# IRIS-EXT-04-BRK_Top.net
KiCad netlist of a schematic drawn in Altium Designer
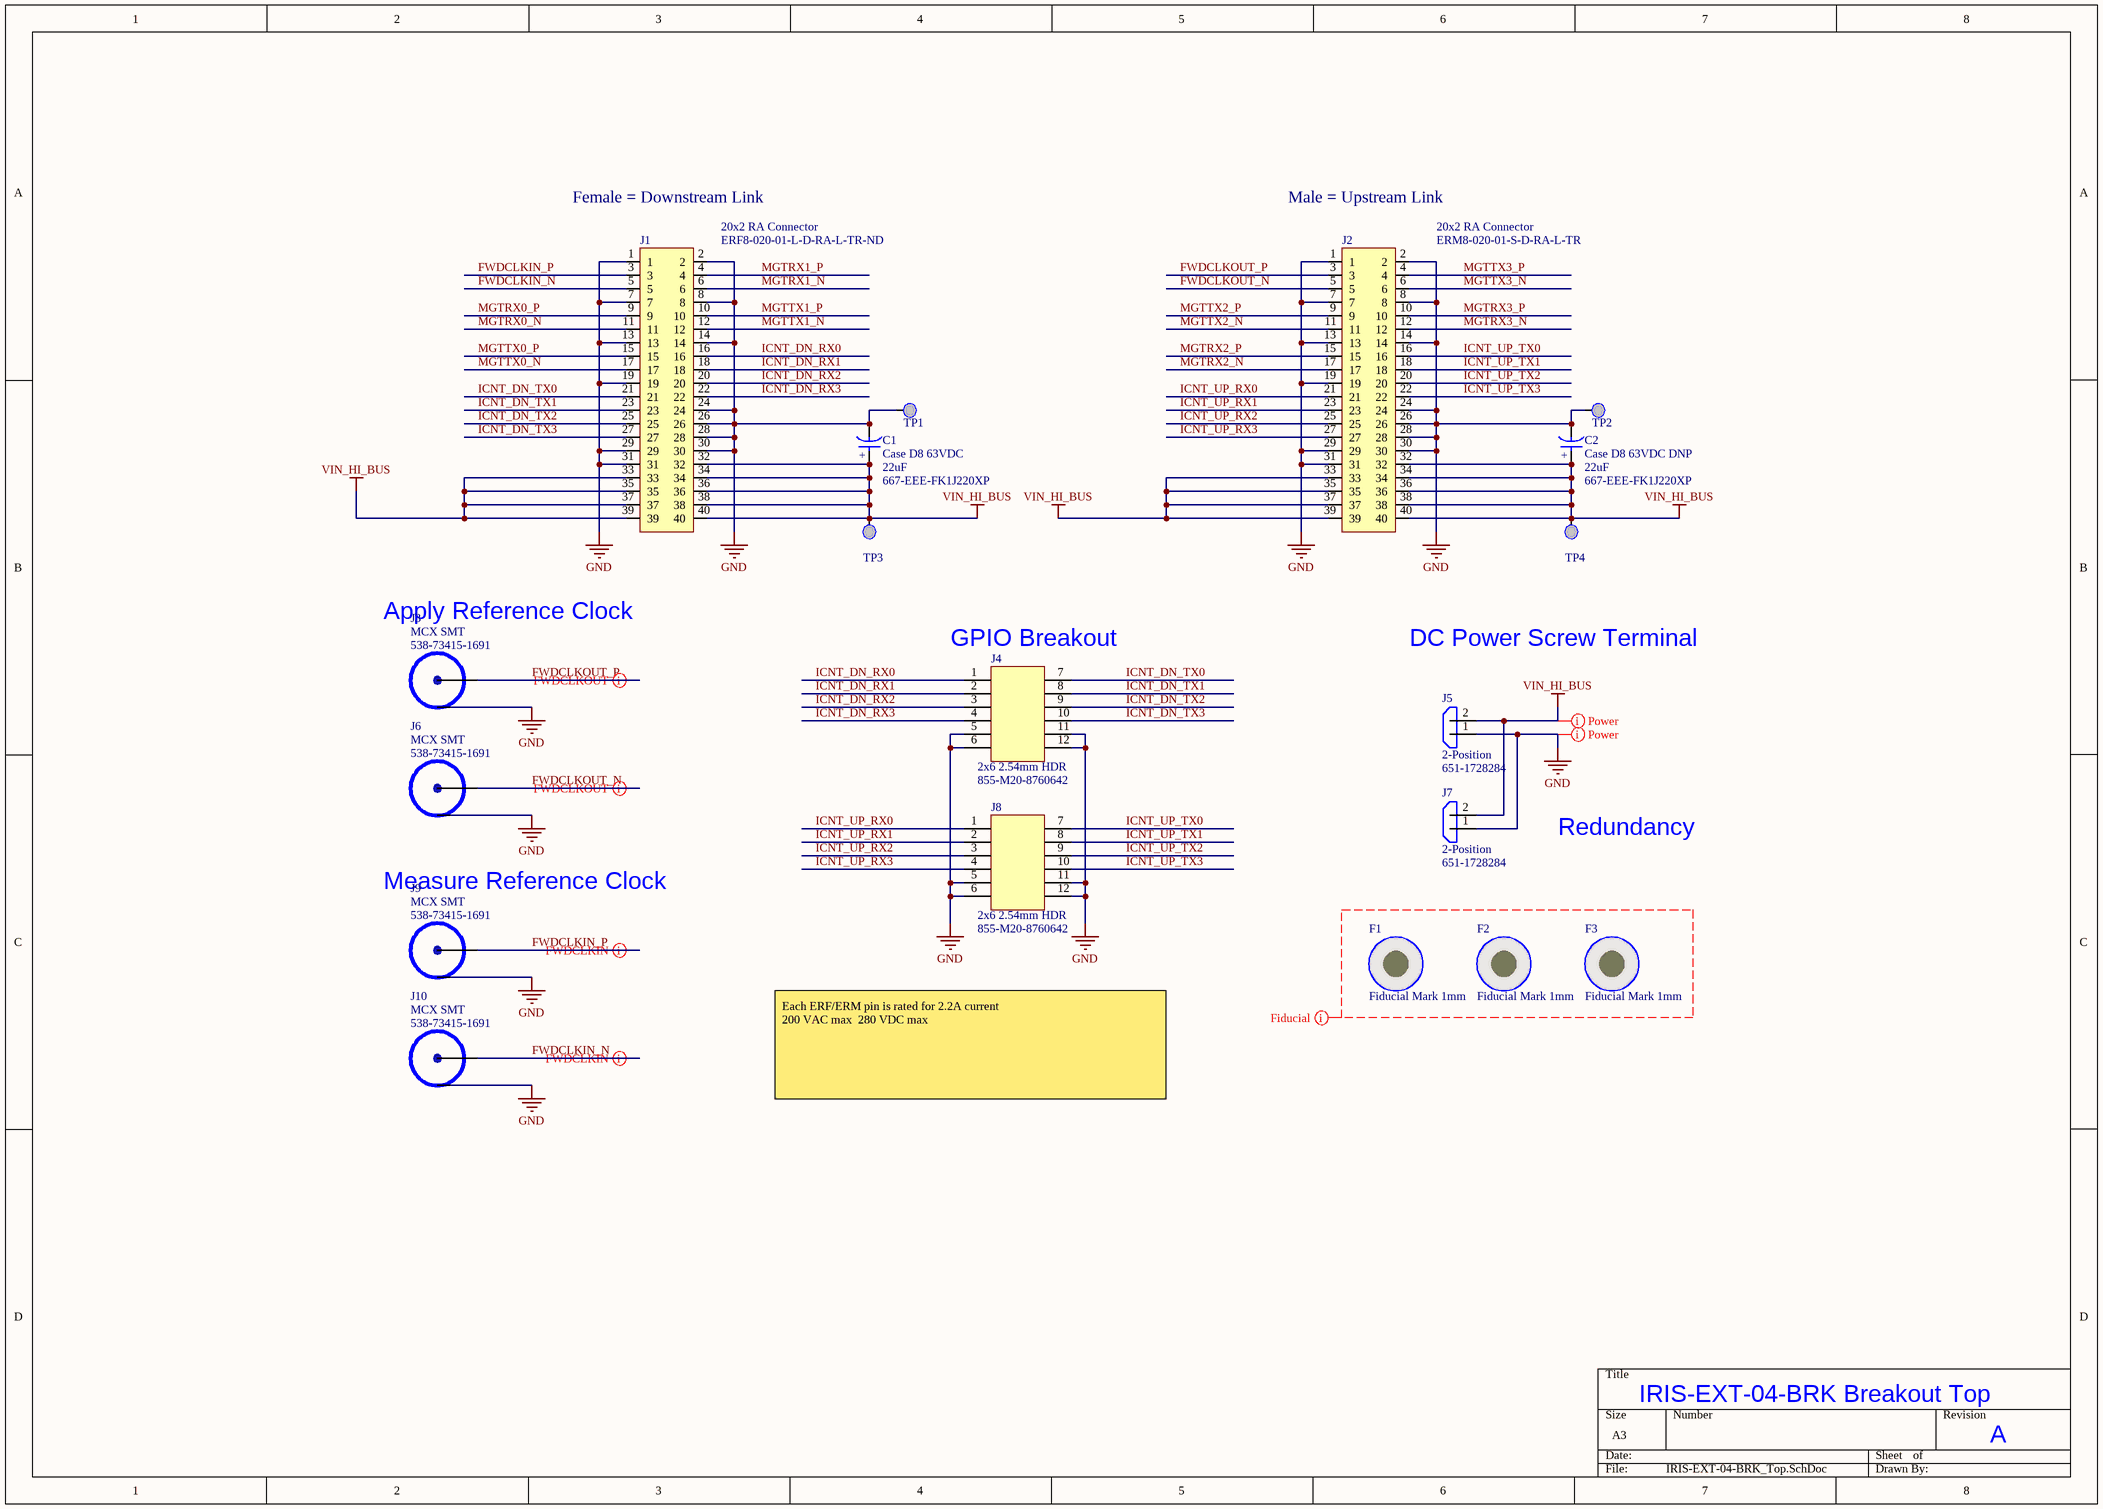
[diagram p0: IRIS-EXT-04-BRK_Top.SchDoc]

(export (version "E")
  (design (tool "Eeschema 10.0.6"))
  (components
    (comp (ref "C1")
      (value "Case D8 63VDC")
      (footprint "Panasonic_SMT_D8")
      (description "Electrolytic SMT Capacitor, Case D8")
      (fields
        (field (name "ALTIUM_VALUE") "22uF")
        (field (name "SUPPLIER PART NUMBER 1") "667-EEE-FK1J220XP")
      )
      (libsource (lib "Skylark_Master") (part "Cap_Electrolytic_SMT_D8"))
    )
    (comp (ref "C2")
      (value "Case D8 63VDC DNP")
      (footprint "Panasonic_SMT_D8")
      (description "Electrolytic SMT Capacitor, Case D8")
      (fields
        (field (name "ALTIUM_VALUE") "22uF")
        (field (name "SUPPLIER PART NUMBER 1") "667-EEE-FK1J220XP")
      )
      (libsource (lib "Skylark_Master") (part "Cap_Electrolytic_SMT_D8"))
    )
    (comp (ref "F1")
      (value "Fiducial Mark 1mm")
      (footprint "1mm_FIDUCIAL")
      (libsource (lib "RNG_Parts") (part "Fiducial-1mm"))
    )
    (comp (ref "F2")
      (value "Fiducial Mark 1mm")
      (footprint "1mm_FIDUCIAL")
      (libsource (lib "RNG_Parts") (part "Fiducial-1mm"))
    )
    (comp (ref "F3")
      (value "Fiducial Mark 1mm")
      (footprint "1mm_FIDUCIAL")
      (libsource (lib "RNG_Parts") (part "Fiducial-1mm"))
    )
    (comp (ref "J1")
      (value "20x2 RA Connector")
      (footprint "ERF8-020-01-L-D-RA-L-TR")
      (description "Samtec ERF8-020 Female Right-Angle with Latch")
      (fields (field (name "SUPPLIER PART NUMBER 1") "ERF8-020-01-L-D-RA-L-TR-ND"))
      (libsource (lib "Skylark_Master") (part "ERF8-020-01-L-D-RA-L-TR"))
    )
    (comp (ref "J2")
      (value "20x2 RA Connector")
      (footprint "ERM8-020-01-S-D-RA-L-TR")
      (description "Samtec ERM8-020 Male Right-Angle with Latch")
      (fields (field (name "SUPPLIER PART NUMBER 1") "ERM8-020-01-S-D-RA-L-TR"))
      (libsource (lib "Skylark_Master") (part "ERM8-020-01-S-D-RA-L-TR"))
    )
    (comp (ref "J3")
      (value "MCX SMT")
      (footprint "Molex-734151691")
      (description "Molex 50 Ohm SMT MCX Jack")
      (fields (field (name "SUPPLIER PART NUMBER 1") "538-73415-1691"))
      (libsource (lib "RNG_Parts") (part "Molex-734151691"))
    )
    (comp (ref "J4")
      (value "2x6 2.54mm HDR")
      (footprint "M20-876-350012")
      (description "Harwin 2.54mm Thru Straight Recepticle")
      (fields (field (name "SUPPLIER PART NUMBER 1") "855-M20-8760642"))
      (libsource (lib "VUUM_Master") (part "M20-8760642"))
    )
    (comp (ref "J5")
      (value "2-Position")
      (footprint "Phoenix-1728284")
      (description "Phoenix Angled Thru Screw Terminal Block 2-Pos")
      (fields (field (name "SUPPLIER PART NUMBER 1") "651-1728284"))
      (libsource (lib "Skylark_Master") (part "Phoenix-1728284"))
    )
    (comp (ref "J6")
      (value "MCX SMT")
      (footprint "Molex-734151691")
      (description "Molex 50 Ohm SMT MCX Jack")
      (fields (field (name "SUPPLIER PART NUMBER 1") "538-73415-1691"))
      (libsource (lib "RNG_Parts") (part "Molex-734151691"))
    )
    (comp (ref "J7")
      (value "2-Position")
      (footprint "Phoenix-1728284")
      (description "Phoenix Angled Thru Screw Terminal Block 2-Pos")
      (fields (field (name "SUPPLIER PART NUMBER 1") "651-1728284"))
      (libsource (lib "Skylark_Master") (part "Phoenix-1728284"))
    )
    (comp (ref "J8")
      (value "2x6 2.54mm HDR")
      (footprint "M20-876-350012")
      (description "Harwin 2.54mm Thru Straight Recepticle")
      (fields (field (name "SUPPLIER PART NUMBER 1") "855-M20-8760642"))
      (libsource (lib "VUUM_Master") (part "M20-8760642"))
    )
    (comp (ref "J9")
      (value "MCX SMT")
      (footprint "Molex-734151691")
      (description "Molex 50 Ohm SMT MCX Jack")
      (fields (field (name "SUPPLIER PART NUMBER 1") "538-73415-1691"))
      (libsource (lib "RNG_Parts") (part "Molex-734151691"))
    )
    (comp (ref "J10")
      (value "MCX SMT")
      (footprint "Molex-734151691")
      (description "Molex 50 Ohm SMT MCX Jack")
      (fields (field (name "SUPPLIER PART NUMBER 1") "538-73415-1691"))
      (libsource (lib "RNG_Parts") (part "Molex-734151691"))
    )
    (comp (ref "TP1")
      (value "Testpoint")
      (footprint "Keystone-Red-TP")
      (description "Red Through Mount Probe Testpoint")
      (libsource (lib "Skylark_Master") (part "Keystone-5000-5004-Red-TP"))
    )
    (comp (ref "TP2")
      (value "Testpoint")
      (footprint "Keystone-Red-TP")
      (description "Red Through Mount Probe Testpoint")
      (libsource (lib "Skylark_Master") (part "Keystone-5000-5004-Red-TP"))
    )
    (comp (ref "TP3")
      (value "Testpoint")
      (footprint "Keystone-Red-TP")
      (description "Red Through Mount Probe Testpoint")
      (libsource (lib "Skylark_Master") (part "Keystone-5000-5004-Red-TP"))
    )
    (comp (ref "TP4")
      (value "Testpoint")
      (footprint "Keystone-Red-TP")
      (description "Red Through Mount Probe Testpoint")
      (libsource (lib "Skylark_Master") (part "Keystone-5000-5004-Red-TP"))
    )
  )
  (nets
    (net (code "1") (name "/FWDCLKIN_N") (class "Default")
      (node (ref "J1") (pin "5") (pinfunction "5_5") (pintype "passive"))
      (node (ref "J10") (pin "1") (pinfunction "SIG_1") (pintype "power_in"))
    )
    (net (code "2") (name "/FWDCLKIN_P") (class "Default")
      (node (ref "J1") (pin "3") (pinfunction "3_3") (pintype "passive"))
      (node (ref "J9") (pin "1") (pinfunction "SIG_1") (pintype "power_in"))
    )
    (net (code "3") (name "/FWDCLKOUT_N") (class "Default")
      (node (ref "J2") (pin "5") (pinfunction "5_5") (pintype "passive"))
      (node (ref "J6") (pin "1") (pinfunction "SIG_1") (pintype "power_in"))
    )
    (net (code "4") (name "/FWDCLKOUT_P") (class "Default")
      (node (ref "J2") (pin "3") (pinfunction "3_3") (pintype "passive"))
      (node (ref "J3") (pin "1") (pinfunction "SIG_1") (pintype "power_in"))
    )
    (net (code "5") (name "/ICNT_DN_RX0") (class "Default")
      (node (ref "J1") (pin "16") (pinfunction "16_16") (pintype "passive"))
      (node (ref "J4") (pin "1") (pinfunction "1_1") (pintype "passive"))
    )
    (net (code "6") (name "/ICNT_DN_RX1") (class "Default")
      (node (ref "J1") (pin "18") (pinfunction "18_18") (pintype "passive"))
      (node (ref "J4") (pin "2") (pinfunction "2_2") (pintype "passive"))
    )
    (net (code "7") (name "/ICNT_DN_RX2") (class "Default")
      (node (ref "J1") (pin "20") (pinfunction "20_20") (pintype "passive"))
      (node (ref "J4") (pin "3") (pinfunction "3_3") (pintype "passive"))
    )
    (net (code "8") (name "/ICNT_DN_RX3") (class "Default")
      (node (ref "J1") (pin "22") (pinfunction "22_22") (pintype "passive"))
      (node (ref "J4") (pin "4") (pinfunction "4_4") (pintype "passive"))
    )
    (net (code "9") (name "/ICNT_DN_TX0") (class "Default")
      (node (ref "J1") (pin "21") (pinfunction "21_21") (pintype "passive"))
      (node (ref "J4") (pin "7") (pinfunction "7_7") (pintype "passive"))
    )
    (net (code "10") (name "/ICNT_DN_TX1") (class "Default")
      (node (ref "J1") (pin "23") (pinfunction "23_23") (pintype "passive"))
      (node (ref "J4") (pin "8") (pinfunction "8_8") (pintype "passive"))
    )
    (net (code "11") (name "/ICNT_DN_TX2") (class "Default")
      (node (ref "J1") (pin "25") (pinfunction "25_25") (pintype "passive"))
      (node (ref "J4") (pin "9") (pinfunction "9_9") (pintype "passive"))
    )
    (net (code "12") (name "/ICNT_DN_TX3") (class "Default")
      (node (ref "J1") (pin "27") (pinfunction "27_27") (pintype "passive"))
      (node (ref "J4") (pin "10") (pinfunction "10_10") (pintype "passive"))
    )
    (net (code "13") (name "/ICNT_UP_RX0") (class "Default")
      (node (ref "J2") (pin "21") (pinfunction "21_21") (pintype "passive"))
      (node (ref "J8") (pin "1") (pinfunction "1_1") (pintype "passive"))
    )
    (net (code "14") (name "/ICNT_UP_RX1") (class "Default")
      (node (ref "J2") (pin "23") (pinfunction "23_23") (pintype "passive"))
      (node (ref "J8") (pin "2") (pinfunction "2_2") (pintype "passive"))
    )
    (net (code "15") (name "/ICNT_UP_RX2") (class "Default")
      (node (ref "J2") (pin "25") (pinfunction "25_25") (pintype "passive"))
      (node (ref "J8") (pin "3") (pinfunction "3_3") (pintype "passive"))
    )
    (net (code "16") (name "/ICNT_UP_RX3") (class "Default")
      (node (ref "J2") (pin "27") (pinfunction "27_27") (pintype "passive"))
      (node (ref "J8") (pin "4") (pinfunction "4_4") (pintype "passive"))
    )
    (net (code "17") (name "/ICNT_UP_TX0") (class "Default")
      (node (ref "J2") (pin "16") (pinfunction "16_16") (pintype "passive"))
      (node (ref "J8") (pin "7") (pinfunction "7_7") (pintype "passive"))
    )
    (net (code "18") (name "/ICNT_UP_TX1") (class "Default")
      (node (ref "J2") (pin "18") (pinfunction "18_18") (pintype "passive"))
      (node (ref "J8") (pin "8") (pinfunction "8_8") (pintype "passive"))
    )
    (net (code "19") (name "/ICNT_UP_TX2") (class "Default")
      (node (ref "J2") (pin "20") (pinfunction "20_20") (pintype "passive"))
      (node (ref "J8") (pin "9") (pinfunction "9_9") (pintype "passive"))
    )
    (net (code "20") (name "/ICNT_UP_TX3") (class "Default")
      (node (ref "J2") (pin "22") (pinfunction "22_22") (pintype "passive"))
      (node (ref "J8") (pin "10") (pinfunction "10_10") (pintype "passive"))
    )
    (net (code "21") (name "/MGTRX0_N") (class "Default")
      (node (ref "J1") (pin "11") (pinfunction "11_11") (pintype "passive"))
    )
    (net (code "22") (name "/MGTRX0_P") (class "Default")
      (node (ref "J1") (pin "9") (pinfunction "9_9") (pintype "passive"))
    )
    (net (code "23") (name "/MGTRX1_N") (class "Default")
      (node (ref "J1") (pin "6") (pinfunction "6_6") (pintype "passive"))
    )
    (net (code "24") (name "/MGTRX1_P") (class "Default")
      (node (ref "J1") (pin "4") (pinfunction "4_4") (pintype "passive"))
    )
    (net (code "25") (name "/MGTRX2_N") (class "Default")
      (node (ref "J2") (pin "17") (pinfunction "17_17") (pintype "passive"))
    )
    (net (code "26") (name "/MGTRX2_P") (class "Default")
      (node (ref "J2") (pin "15") (pinfunction "15_15") (pintype "passive"))
    )
    (net (code "27") (name "/MGTRX3_N") (class "Default")
      (node (ref "J2") (pin "12") (pinfunction "12_12") (pintype "passive"))
    )
    (net (code "28") (name "/MGTRX3_P") (class "Default")
      (node (ref "J2") (pin "10") (pinfunction "10_10") (pintype "passive"))
    )
    (net (code "29") (name "/MGTTX0_N") (class "Default")
      (node (ref "J1") (pin "17") (pinfunction "17_17") (pintype "passive"))
    )
    (net (code "30") (name "/MGTTX0_P") (class "Default")
      (node (ref "J1") (pin "15") (pinfunction "15_15") (pintype "passive"))
    )
    (net (code "31") (name "/MGTTX1_N") (class "Default")
      (node (ref "J1") (pin "12") (pinfunction "12_12") (pintype "passive"))
    )
    (net (code "32") (name "/MGTTX1_P") (class "Default")
      (node (ref "J1") (pin "10") (pinfunction "10_10") (pintype "passive"))
    )
    (net (code "33") (name "/MGTTX2_N") (class "Default")
      (node (ref "J2") (pin "11") (pinfunction "11_11") (pintype "passive"))
    )
    (net (code "34") (name "/MGTTX2_P") (class "Default")
      (node (ref "J2") (pin "9") (pinfunction "9_9") (pintype "passive"))
    )
    (net (code "35") (name "/MGTTX3_N") (class "Default")
      (node (ref "J2") (pin "6") (pinfunction "6_6") (pintype "passive"))
    )
    (net (code "36") (name "/MGTTX3_P") (class "Default")
      (node (ref "J2") (pin "4") (pinfunction "4_4") (pintype "passive"))
    )
    (net (code "37") (name "GND") (class "Default")
      (node (ref "C1") (pin "K") (pinfunction "K_K") (pintype "passive"))
      (node (ref "C2") (pin "K") (pinfunction "K_K") (pintype "passive"))
      (node (ref "J1") (pin "1") (pinfunction "1_1") (pintype "passive"))
      (node (ref "J1") (pin "13") (pinfunction "13_13") (pintype "passive"))
      (node (ref "J1") (pin "14") (pinfunction "14_14") (pintype "passive"))
      (node (ref "J1") (pin "19") (pinfunction "19_19") (pintype "passive"))
      (node (ref "J1") (pin "2") (pinfunction "2_2") (pintype "passive"))
      (node (ref "J1") (pin "24") (pinfunction "24_24") (pintype "passive"))
      (node (ref "J1") (pin "26") (pinfunction "26_26") (pintype "passive"))
      (node (ref "J1") (pin "28") (pinfunction "28_28") (pintype "passive"))
      (node (ref "J1") (pin "29") (pinfunction "29_29") (pintype "passive"))
      (node (ref "J1") (pin "30") (pinfunction "30_30") (pintype "passive"))
      (node (ref "J1") (pin "31") (pinfunction "31_31") (pintype "passive"))
      (node (ref "J1") (pin "7") (pinfunction "7_7") (pintype "passive"))
      (node (ref "J1") (pin "8") (pinfunction "8_8") (pintype "passive"))
      (node (ref "J10") (pin "0") (pinfunction "GND_0") (pintype "power_in"))
      (node (ref "J2") (pin "1") (pinfunction "1_1") (pintype "passive"))
      (node (ref "J2") (pin "13") (pinfunction "13_13") (pintype "passive"))
      (node (ref "J2") (pin "14") (pinfunction "14_14") (pintype "passive"))
      (node (ref "J2") (pin "19") (pinfunction "19_19") (pintype "passive"))
      (node (ref "J2") (pin "2") (pinfunction "2_2") (pintype "passive"))
      (node (ref "J2") (pin "24") (pinfunction "24_24") (pintype "passive"))
      (node (ref "J2") (pin "26") (pinfunction "26_26") (pintype "passive"))
      (node (ref "J2") (pin "28") (pinfunction "28_28") (pintype "passive"))
      (node (ref "J2") (pin "29") (pinfunction "29_29") (pintype "passive"))
      (node (ref "J2") (pin "30") (pinfunction "30_30") (pintype "passive"))
      (node (ref "J2") (pin "31") (pinfunction "31_31") (pintype "passive"))
      (node (ref "J2") (pin "7") (pinfunction "7_7") (pintype "passive"))
      (node (ref "J2") (pin "8") (pinfunction "8_8") (pintype "passive"))
      (node (ref "J3") (pin "0") (pinfunction "GND_0") (pintype "power_in"))
      (node (ref "J4") (pin "11") (pinfunction "11_11") (pintype "passive"))
      (node (ref "J4") (pin "12") (pinfunction "12_12") (pintype "passive"))
      (node (ref "J4") (pin "5") (pinfunction "5_5") (pintype "passive"))
      (node (ref "J4") (pin "6") (pinfunction "6_6") (pintype "passive"))
      (node (ref "J5") (pin "1") (pinfunction "1_1") (pintype "passive"))
      (node (ref "J6") (pin "0") (pinfunction "GND_0") (pintype "power_in"))
      (node (ref "J7") (pin "1") (pinfunction "1_1") (pintype "passive"))
      (node (ref "J8") (pin "11") (pinfunction "11_11") (pintype "passive"))
      (node (ref "J8") (pin "12") (pinfunction "12_12") (pintype "passive"))
      (node (ref "J8") (pin "5") (pinfunction "5_5") (pintype "passive"))
      (node (ref "J8") (pin "6") (pinfunction "6_6") (pintype "passive"))
      (node (ref "J9") (pin "0") (pinfunction "GND_0") (pintype "power_in"))
      (node (ref "TP1") (pin "0") (pinfunction "0_0") (pintype "passive"))
      (node (ref "TP2") (pin "0") (pinfunction "0_0") (pintype "passive"))
    )
    (net (code "38") (name "VIN_HI_BUS") (class "Default")
      (node (ref "C1") (pin "A") (pinfunction "A_A") (pintype "passive"))
      (node (ref "C2") (pin "A") (pinfunction "A_A") (pintype "passive"))
      (node (ref "J1") (pin "32") (pinfunction "32_32") (pintype "passive"))
      (node (ref "J1") (pin "33") (pinfunction "33_33") (pintype "passive"))
      (node (ref "J1") (pin "34") (pinfunction "34_34") (pintype "passive"))
      (node (ref "J1") (pin "35") (pinfunction "35_35") (pintype "passive"))
      (node (ref "J1") (pin "36") (pinfunction "36_36") (pintype "passive"))
      (node (ref "J1") (pin "37") (pinfunction "37_37") (pintype "passive"))
      (node (ref "J1") (pin "38") (pinfunction "38_38") (pintype "passive"))
      (node (ref "J1") (pin "39") (pinfunction "39_39") (pintype "passive"))
      (node (ref "J1") (pin "40") (pinfunction "40_40") (pintype "passive"))
      (node (ref "J2") (pin "32") (pinfunction "32_32") (pintype "passive"))
      (node (ref "J2") (pin "33") (pinfunction "33_33") (pintype "passive"))
      (node (ref "J2") (pin "34") (pinfunction "34_34") (pintype "passive"))
      (node (ref "J2") (pin "35") (pinfunction "35_35") (pintype "passive"))
      (node (ref "J2") (pin "36") (pinfunction "36_36") (pintype "passive"))
      (node (ref "J2") (pin "37") (pinfunction "37_37") (pintype "passive"))
      (node (ref "J2") (pin "38") (pinfunction "38_38") (pintype "passive"))
      (node (ref "J2") (pin "39") (pinfunction "39_39") (pintype "passive"))
      (node (ref "J2") (pin "40") (pinfunction "40_40") (pintype "passive"))
      (node (ref "J5") (pin "2") (pinfunction "2_2") (pintype "passive"))
      (node (ref "J7") (pin "2") (pinfunction "2_2") (pintype "passive"))
      (node (ref "TP3") (pin "0") (pinfunction "0_0") (pintype "passive"))
      (node (ref "TP4") (pin "0") (pinfunction "0_0") (pintype "passive"))
    )
  )
)
